# SCH_Placa-MME_2025-02-16.net
KiCad netlist of a schematic drawn in EasyEDA
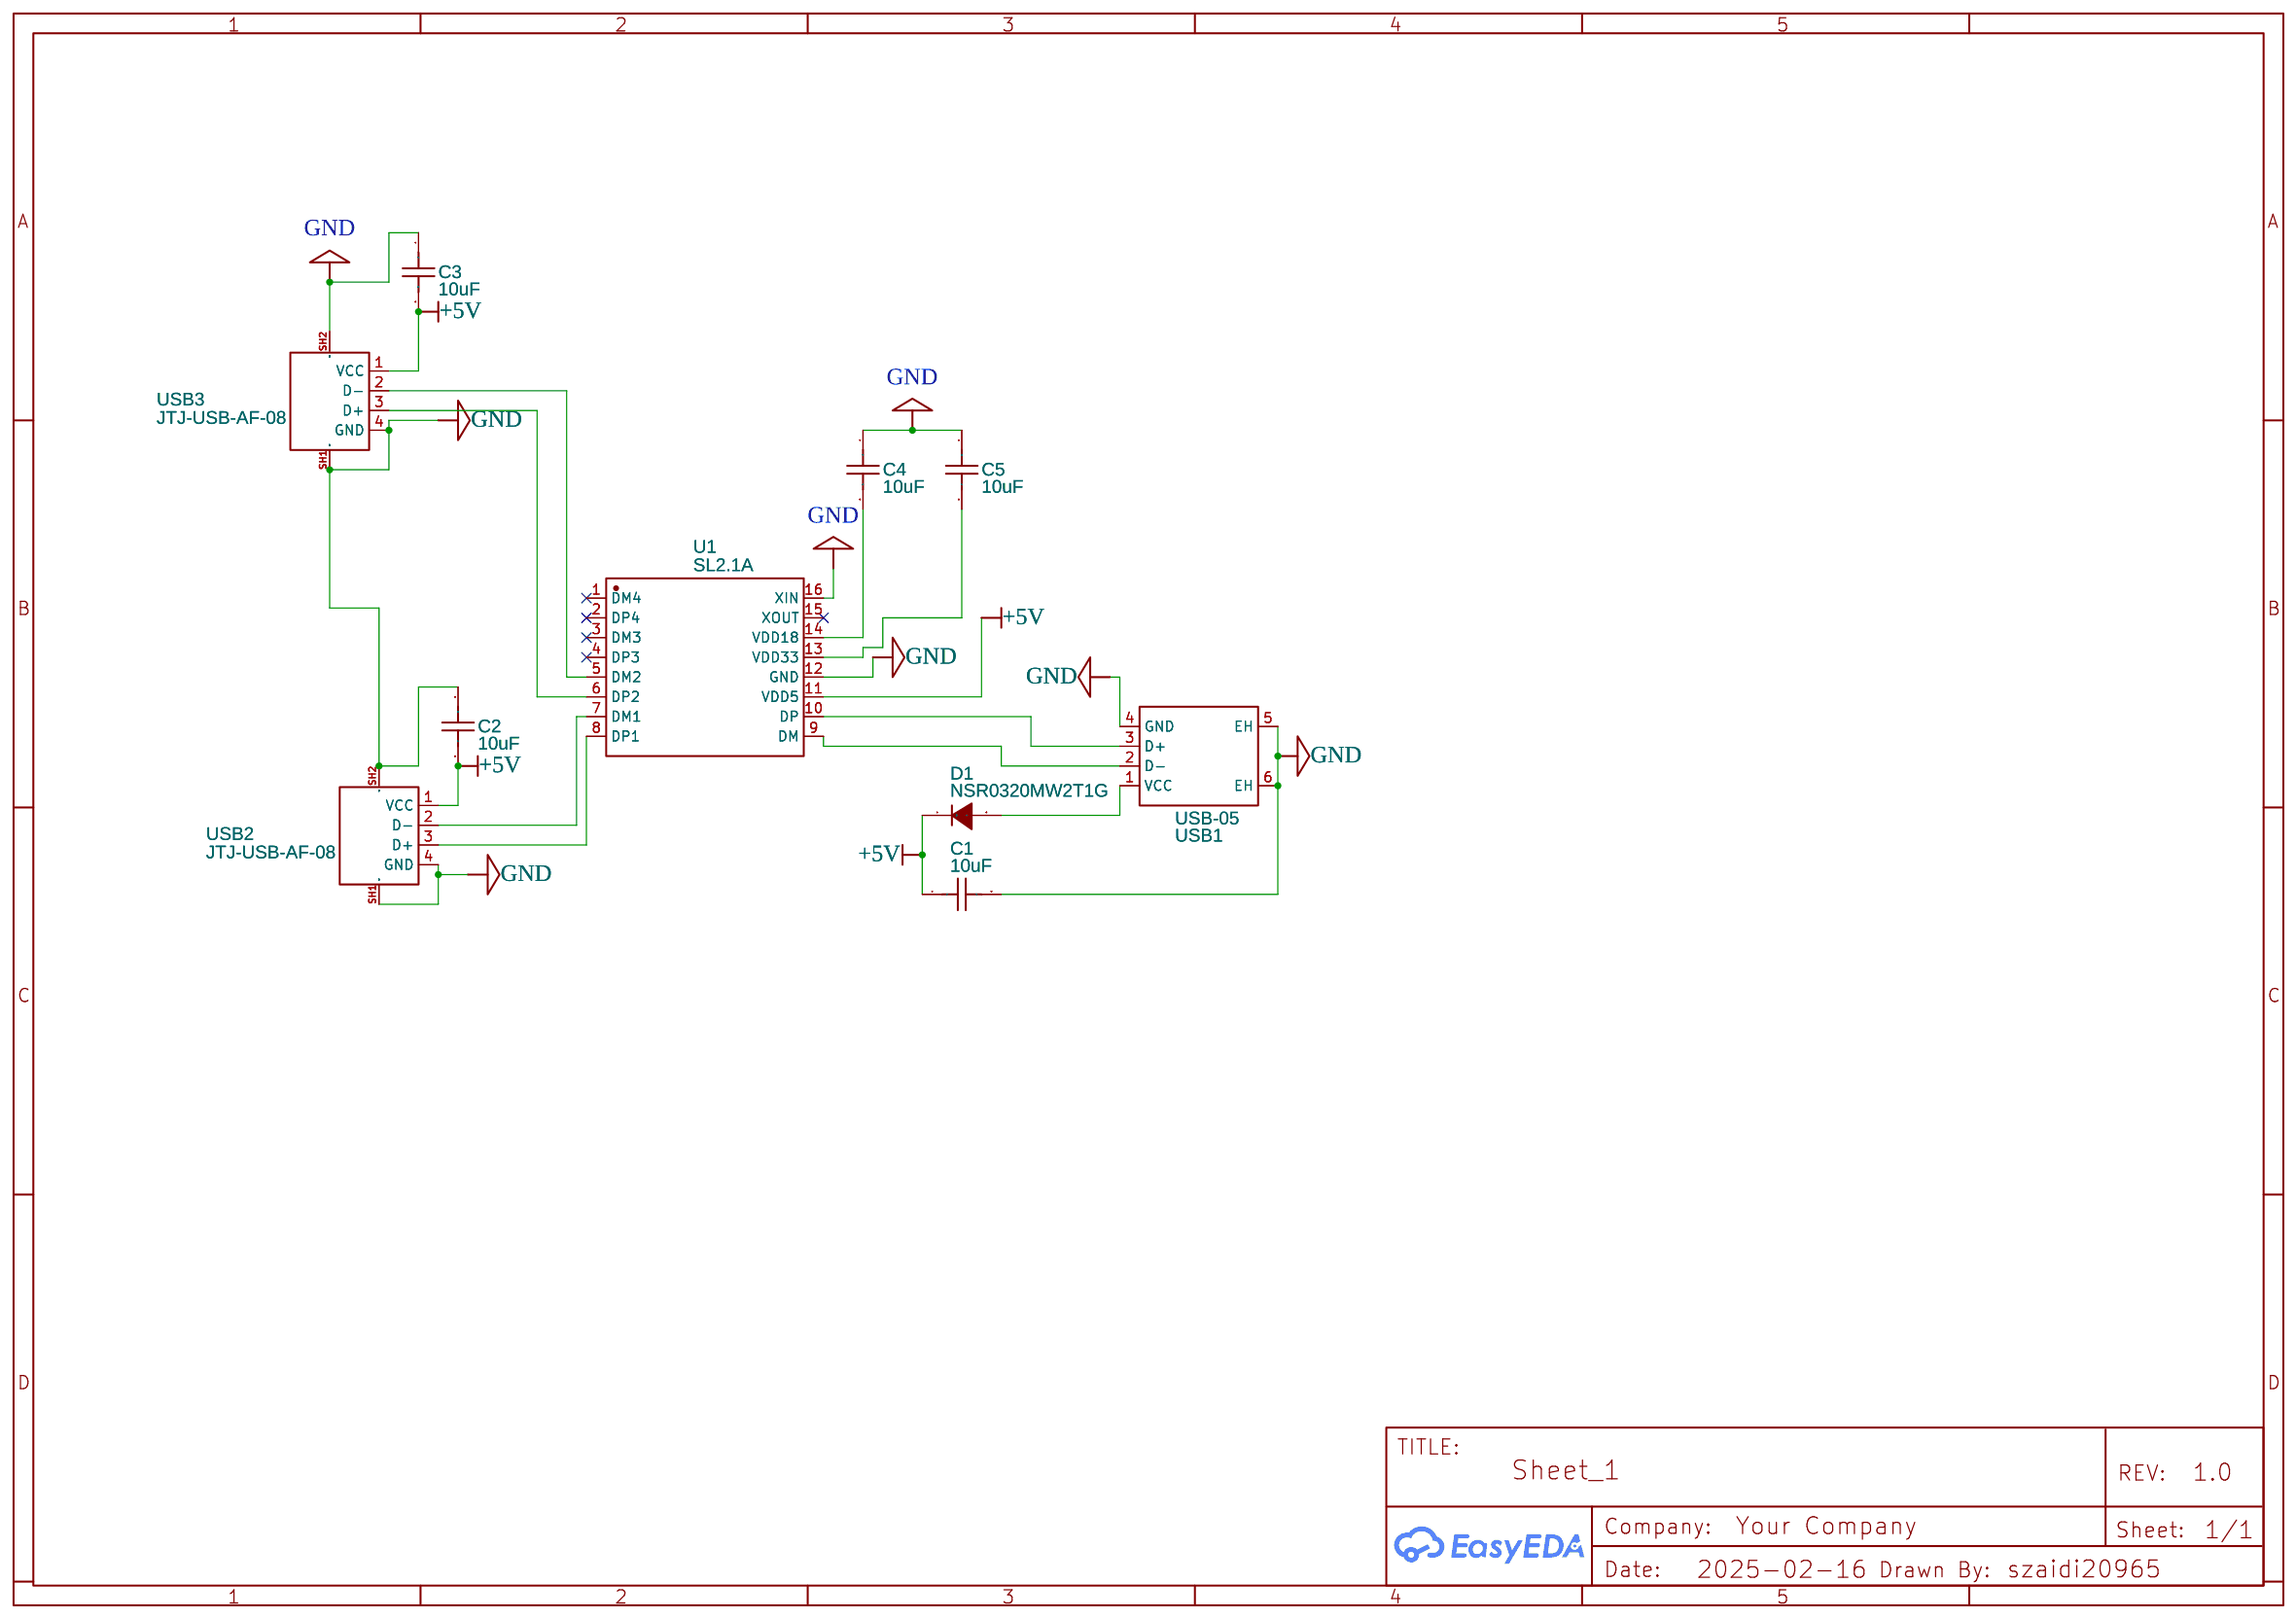
[diagram p0: schematic sheet]

(export (version "E")
  (design (tool "Eeschema 10.0.6"))
  (components
    (comp (ref "C1")
      (value "10uF")
      (fields
        (field (name "Manufacturer Part") "CL10A106KP8NNNC")
        (field (name "Manufacturer") "SAMSUNG(三星)")
      )
      (libsource (lib "") (part "CL10A106KP8NNNC_1"))
    )
    (comp (ref "C2")
      (value "10uF")
      (fields
        (field (name "Manufacturer Part") "CL10A106KP8NNNC")
        (field (name "Manufacturer") "SAMSUNG(三星)")
      )
      (libsource (lib "") (part "CL10A106KP8NNNC"))
    )
    (comp (ref "C3")
      (value "10uF")
      (fields
        (field (name "Manufacturer Part") "CL10A106KP8NNNC")
        (field (name "Manufacturer") "SAMSUNG(三星)")
      )
      (libsource (lib "") (part "CL10A106KP8NNNC"))
    )
    (comp (ref "C4")
      (value "10uF")
      (fields
        (field (name "Manufacturer Part") "CL10A106KP8NNNC")
        (field (name "Manufacturer") "SAMSUNG(三星)")
      )
      (libsource (lib "") (part "CL10A106KP8NNNC"))
    )
    (comp (ref "C5")
      (value "10uF")
      (fields
        (field (name "Manufacturer Part") "CL10A106KP8NNNC")
        (field (name "Manufacturer") "SAMSUNG(三星)")
      )
      (libsource (lib "") (part "CL10A106KP8NNNC"))
    )
    (comp (ref "D1")
      (value "NSR0320MW2T1G")
      (fields (field (name "Manufacturer") "onsemi(安森美)"))
      (libsource (lib "") (part "NSR0320MW2T1G"))
    )
    (comp (ref "U1")
      (value "SL2.1A")
      (fields (field (name "Manufacturer") "CoreChips(和芯润德)"))
      (libsource (lib "") (part "SL2.1A"))
    )
    (comp (ref "USB1")
      (value "USB-05")
      (fields (field (name "Manufacturer") "SOFNG(硕方)"))
      (libsource (lib "") (part "USB-05"))
    )
    (comp (ref "USB2")
      (value "JTJ-USB-AF-08")
      (fields (field (name "Manufacturer Part") "902-131A1011D10100") (field (name "Manufacturer") "精拓金"))
      (libsource (lib "") (part "JTJ-USB-AF-08"))
    )
    (comp (ref "USB3")
      (value "JTJ-USB-AF-08")
      (fields (field (name "Manufacturer Part") "902-131A1011D10100") (field (name "Manufacturer") "精拓金"))
      (libsource (lib "") (part "JTJ-USB-AF-08"))
    )
  )
  (nets
    (net (code "1") (name "+5V") (class "Default")
      (node (ref "C1") (pin "1") (pinfunction "1_1") (pintype "unspecified"))
      (node (ref "C2") (pin "2") (pinfunction "2_2") (pintype "unspecified"))
      (node (ref "C3") (pin "2") (pinfunction "2_2") (pintype "unspecified"))
      (node (ref "D1") (pin "1") (pinfunction "C_1") (pintype "unspecified"))
      (node (ref "U1") (pin "11") (pinfunction "VDD5_11") (pintype "unspecified"))
      (node (ref "USB2") (pin "1") (pinfunction "VCC_1") (pintype "input"))
      (node (ref "USB3") (pin "1") (pinfunction "VCC_1") (pintype "input"))
    )
    (net (code "2") (name "GND") (class "Default")
      (node (ref "C1") (pin "2") (pinfunction "2_2") (pintype "unspecified"))
      (node (ref "C2") (pin "1") (pinfunction "1_1") (pintype "unspecified"))
      (node (ref "C3") (pin "1") (pinfunction "1_1") (pintype "unspecified"))
      (node (ref "C4") (pin "1") (pinfunction "1_1") (pintype "unspecified"))
      (node (ref "C5") (pin "1") (pinfunction "1_1") (pintype "unspecified"))
      (node (ref "U1") (pin "12") (pinfunction "GND_12") (pintype "unspecified"))
      (node (ref "U1") (pin "16") (pinfunction "XIN_16") (pintype "unspecified"))
      (node (ref "USB1") (pin "4") (pinfunction "GND_4") (pintype "input"))
      (node (ref "USB1") (pin "5") (pinfunction "EH_5") (pintype "unspecified"))
      (node (ref "USB1") (pin "6") (pinfunction "EH_6") (pintype "unspecified"))
      (node (ref "USB2") (pin "4") (pinfunction "GND_4") (pintype "input"))
      (node (ref "USB2") (pin "SH1") (pinfunction "SH1_SH1") (pintype "unspecified"))
      (node (ref "USB2") (pin "SH2") (pinfunction "SH2_SH2") (pintype "unspecified"))
      (node (ref "USB3") (pin "4") (pinfunction "GND_4") (pintype "input"))
      (node (ref "USB3") (pin "SH1") (pinfunction "SH1_SH1") (pintype "unspecified"))
      (node (ref "USB3") (pin "SH2") (pinfunction "SH2_SH2") (pintype "unspecified"))
    )
    (net (code "3") (name "Net-(D1-A)") (class "Default")
      (node (ref "D1") (pin "2") (pinfunction "A_2") (pintype "unspecified"))
      (node (ref "USB1") (pin "1") (pinfunction "VCC_1") (pintype "input"))
    )
    (net (code "4") (name "Net-(U1-DM)") (class "Default")
      (node (ref "U1") (pin "9") (pinfunction "DM_9") (pintype "unspecified"))
      (node (ref "USB1") (pin "2") (pinfunction "D-_2") (pintype "input"))
    )
    (net (code "5") (name "Net-(U1-DM1)") (class "Default")
      (node (ref "U1") (pin "7") (pinfunction "DM1_7") (pintype "unspecified"))
      (node (ref "USB2") (pin "2") (pinfunction "D-_2") (pintype "input"))
    )
    (net (code "6") (name "Net-(U1-DM2)") (class "Default")
      (node (ref "U1") (pin "5") (pinfunction "DM2_5") (pintype "unspecified"))
      (node (ref "USB3") (pin "2") (pinfunction "D-_2") (pintype "input"))
    )
    (net (code "7") (name "Net-(U1-DP)") (class "Default")
      (node (ref "U1") (pin "10") (pinfunction "DP_10") (pintype "unspecified"))
      (node (ref "USB1") (pin "3") (pinfunction "D+_3") (pintype "input"))
    )
    (net (code "8") (name "Net-(U1-DP1)") (class "Default")
      (node (ref "U1") (pin "8") (pinfunction "DP1_8") (pintype "unspecified"))
      (node (ref "USB2") (pin "3") (pinfunction "D+_3") (pintype "input"))
    )
    (net (code "9") (name "Net-(U1-DP2)") (class "Default")
      (node (ref "U1") (pin "6") (pinfunction "DP2_6") (pintype "unspecified"))
      (node (ref "USB3") (pin "3") (pinfunction "D+_3") (pintype "input"))
    )
    (net (code "10") (name "Net-(U1-VDD18)") (class "Default")
      (node (ref "C4") (pin "2") (pinfunction "2_2") (pintype "unspecified"))
      (node (ref "U1") (pin "14") (pinfunction "VDD18_14") (pintype "unspecified"))
    )
    (net (code "11") (name "Net-(U1-VDD33)") (class "Default")
      (node (ref "C5") (pin "2") (pinfunction "2_2") (pintype "unspecified"))
      (node (ref "U1") (pin "13") (pinfunction "VDD33_13") (pintype "unspecified"))
    )
    (net (code "12") (name "unconnected-(U1-DM3-Pad3)") (class "Default")
      (node (ref "U1") (pin "3") (pinfunction "DM3_3") (pintype "unspecified+no_connect"))
    )
    (net (code "13") (name "unconnected-(U1-DM4-Pad1)") (class "Default")
      (node (ref "U1") (pin "1") (pinfunction "DM4_1") (pintype "unspecified+no_connect"))
    )
    (net (code "14") (name "unconnected-(U1-DP3-Pad4)") (class "Default")
      (node (ref "U1") (pin "4") (pinfunction "DP3_4") (pintype "unspecified+no_connect"))
    )
    (net (code "15") (name "unconnected-(U1-DP4-Pad2)") (class "Default")
      (node (ref "U1") (pin "2") (pinfunction "DP4_2") (pintype "unspecified+no_connect"))
    )
    (net (code "16") (name "unconnected-(U1-XOUT-Pad15)") (class "Default")
      (node (ref "U1") (pin "15") (pinfunction "XOUT_15") (pintype "unspecified+no_connect"))
    )
  )
)
